# ESP1SH.net
KiCad netlist of a schematic drawn in EAGLE
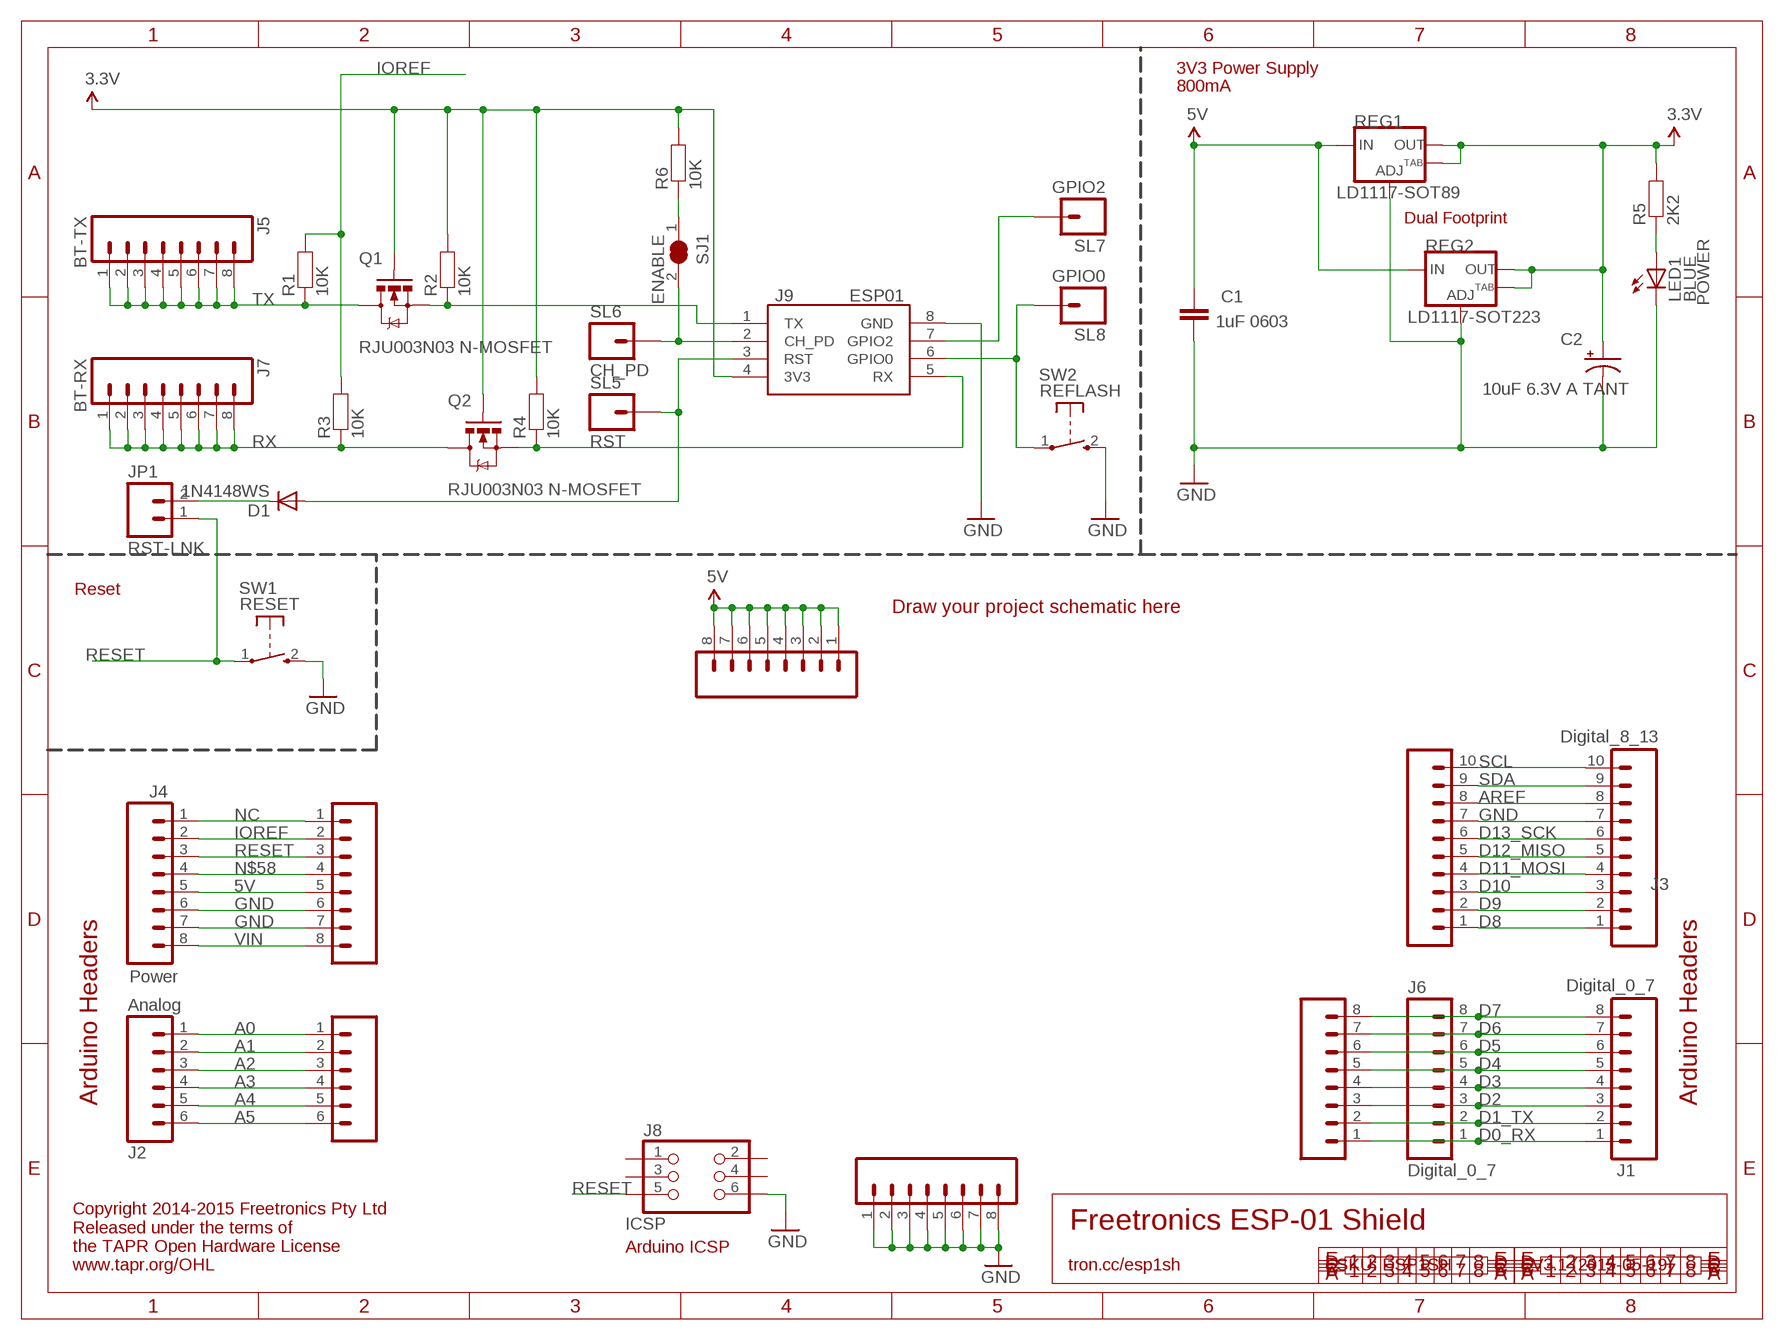
[diagram p0: schematic, sheet 1]

(export (version "E")
  (design (tool "Eeschema 10.0.6"))
  (components
    (comp (ref "C1")
      (value "1uF 0603")
      (footprint "eagle-import:0603")
      (libsource (lib "eagle-import") (part "CAP0603"))
    )
    (comp (ref "C2")
      (value "10uF 6.3V A TANT")
      (footprint "eagle-import:EIA3216")
      (libsource (lib "eagle-import") (part "CAP_POL1206"))
    )
    (comp (ref "D1")
      (value "1N4148WS")
      (footprint "eagle-import:SOD-323")
      (libsource (lib "eagle-import") (part "DIODESOD"))
    )
    (comp (ref "J1")
      (value "Digital_0_7")
      (footprint "eagle-import:1X08")
      (libsource (lib "eagle-import") (part "M08"))
    )
    (comp (ref "J2")
      (value "Analog")
      (footprint "eagle-import:1X06")
      (libsource (lib "eagle-import") (part "M06SIP"))
    )
    (comp (ref "J3")
      (value "Digital_8_13")
      (footprint "eagle-import:1X10")
      (libsource (lib "eagle-import") (part "M100.1"))
    )
    (comp (ref "J4")
      (value "Power")
      (footprint "eagle-import:1X08")
      (libsource (lib "eagle-import") (part "M08"))
    )
    (comp (ref "J5")
      (value "BT-TX")
      (footprint "eagle-import:1X08")
      (libsource (lib "eagle-import") (part "freetronics-original_M08"))
    )
    (comp (ref "J6")
      (value "Digital_0_7")
      (footprint "eagle-import:1X08")
      (libsource (lib "eagle-import") (part "freetronics-original_M08"))
    )
    (comp (ref "J7")
      (value "BT-RX")
      (footprint "eagle-import:1X08")
      (libsource (lib "eagle-import") (part "freetronics-original_M08"))
    )
    (comp (ref "J8")
      (value "ICSP")
      (footprint "eagle-import:2X03PTH")
      (libsource (lib "eagle-import") (part "ICSPPTH"))
    )
    (comp (ref "J9")
      (value "ESP01")
      (footprint "eagle-import:ESP01")
      (libsource (lib "eagle-import") (part "ESP01"))
    )
    (comp (ref "JP1")
      (value "RST-LNK")
      (footprint "eagle-import:1X02")
      (libsource (lib "eagle-import") (part "M02PTH"))
    )
    (comp (ref "LED1")
      (value "BLUE")
      (footprint "eagle-import:LED-0603")
      (libsource (lib "eagle-import") (part "LED0603"))
    )
    (comp (ref "Q1")
      (value "RJU003N03 N-MOSFET")
      (footprint "eagle-import:SOT32-3")
      (libsource (lib "eagle-import") (part "MOSFET-NSOT-323"))
    )
    (comp (ref "Q2")
      (value "RJU003N03 N-MOSFET")
      (footprint "eagle-import:SOT32-3")
      (libsource (lib "eagle-import") (part "MOSFET-NSOT-323"))
    )
    (comp (ref "R1")
      (value "10K")
      (footprint "eagle-import:0603")
      (libsource (lib "eagle-import") (part "RESISTOR0603"))
    )
    (comp (ref "R2")
      (value "10K")
      (footprint "eagle-import:0603")
      (libsource (lib "eagle-import") (part "RESISTOR0603"))
    )
    (comp (ref "R3")
      (value "10K")
      (footprint "eagle-import:0603")
      (libsource (lib "eagle-import") (part "RESISTOR0603"))
    )
    (comp (ref "R4")
      (value "10K")
      (footprint "eagle-import:0603")
      (libsource (lib "eagle-import") (part "RESISTOR0603"))
    )
    (comp (ref "R5")
      (value "2K2")
      (footprint "eagle-import:0603")
      (libsource (lib "eagle-import") (part "RESISTOR0603"))
    )
    (comp (ref "R6")
      (value "10K")
      (footprint "eagle-import:0603")
      (libsource (lib "eagle-import") (part "RESISTOR0603"))
    )
    (comp (ref "REG1")
      (value "LD1117-SOT89")
      (footprint "eagle-import:SOT89")
      (libsource (lib "eagle-import") (part "V_REG_LM1117SOT89"))
    )
    (comp (ref "REG2")
      (value "LD1117-SOT223")
      (footprint "eagle-import:SOT223")
      (libsource (lib "eagle-import") (part "V_REG_LM1117SOT223"))
    )
    (comp (ref "SJ1")
      (value "ENABLE")
      (footprint "eagle-import:SJC")
      (libsource (lib "eagle-import") (part "SJCN"))
    )
    (comp (ref "SL1")
      (value "Digital_0_7")
      (footprint "eagle-import:1X08")
      (libsource (lib "eagle-import") (part "M08"))
    )
    (comp (ref "SL2")
      (value "Analog")
      (footprint "eagle-import:1X06")
      (libsource (lib "eagle-import") (part "M06SIP"))
    )
    (comp (ref "SL3")
      (value "Digital_8_13")
      (footprint "eagle-import:1X10")
      (libsource (lib "eagle-import") (part "M100.1"))
    )
    (comp (ref "SL4")
      (value "Power")
      (footprint "eagle-import:1X08")
      (libsource (lib "eagle-import") (part "M08"))
    )
    (comp (ref "SL5")
      (value "RST")
      (footprint "eagle-import:1X01")
      (libsource (lib "eagle-import") (part "M01PTH"))
    )
    (comp (ref "SL6")
      (value "CH_PD")
      (footprint "eagle-import:1X01")
      (libsource (lib "eagle-import") (part "M01PTH"))
    )
    (comp (ref "SL7")
      (value "GPIO2")
      (footprint "eagle-import:1X01")
      (libsource (lib "eagle-import") (part "M01PTH"))
    )
    (comp (ref "SL8")
      (value "GPIO0")
      (footprint "eagle-import:1X01")
      (libsource (lib "eagle-import") (part "M01PTH"))
    )
    (comp (ref "SL9")
      (value "GND")
      (footprint "eagle-import:1X08")
      (libsource (lib "eagle-import") (part "M08"))
    )
    (comp (ref "SL10")
      (value "5V")
      (footprint "eagle-import:1X08")
      (libsource (lib "eagle-import") (part "M08"))
    )
    (comp (ref "SW1")
      (value "RESET")
      (footprint "eagle-import:TACTILE_SWITCH_SMD_2PIN_TINY")
      (libsource (lib "eagle-import") (part "TAC_SWITCH_2PIN"))
    )
    (comp (ref "SW2")
      (value "REFLASH")
      (footprint "eagle-import:TACTILE_SWITCH_SMD_2PIN_TINY")
      (libsource (lib "eagle-import") (part "TAC_SWITCH_2PIN"))
    )
  )
  (nets
    (net (code "1") (name "/A0") (class "Default")
      (node (ref "J2") (pin "1") (pinfunction "1_1") (pintype "passive"))
      (node (ref "SL2") (pin "1") (pinfunction "1_1") (pintype "passive"))
    )
    (net (code "2") (name "/A1") (class "Default")
      (node (ref "J2") (pin "2") (pinfunction "2_2") (pintype "passive"))
      (node (ref "SL2") (pin "2") (pinfunction "2_2") (pintype "passive"))
    )
    (net (code "3") (name "/A2") (class "Default")
      (node (ref "J2") (pin "3") (pinfunction "3_3") (pintype "passive"))
      (node (ref "SL2") (pin "3") (pinfunction "3_3") (pintype "passive"))
    )
    (net (code "4") (name "/A3") (class "Default")
      (node (ref "J2") (pin "4") (pinfunction "4_4") (pintype "passive"))
      (node (ref "SL2") (pin "4") (pinfunction "4_4") (pintype "passive"))
    )
    (net (code "5") (name "/A4") (class "Default")
      (node (ref "J2") (pin "5") (pinfunction "5_5") (pintype "passive"))
      (node (ref "SL2") (pin "5") (pinfunction "5_5") (pintype "passive"))
    )
    (net (code "6") (name "/A5") (class "Default")
      (node (ref "J2") (pin "6") (pinfunction "6_6") (pintype "passive"))
      (node (ref "SL2") (pin "6") (pinfunction "6_6") (pintype "passive"))
    )
    (net (code "7") (name "/AREF") (class "Default")
      (node (ref "J3") (pin "8") (pinfunction "8_8") (pintype "passive"))
      (node (ref "SL3") (pin "8") (pinfunction "8_8") (pintype "passive"))
    )
    (net (code "8") (name "/D0_RX") (class "Default")
      (node (ref "J1") (pin "1") (pinfunction "1_1") (pintype "passive"))
      (node (ref "J6") (pin "1") (pinfunction "1_1") (pintype "passive"))
      (node (ref "SL1") (pin "1") (pinfunction "1_1") (pintype "passive"))
    )
    (net (code "9") (name "/D1_TX") (class "Default")
      (node (ref "J1") (pin "2") (pinfunction "2_2") (pintype "passive"))
      (node (ref "J6") (pin "2") (pinfunction "2_2") (pintype "passive"))
      (node (ref "SL1") (pin "2") (pinfunction "2_2") (pintype "passive"))
    )
    (net (code "10") (name "/D2") (class "Default")
      (node (ref "J1") (pin "3") (pinfunction "3_3") (pintype "passive"))
      (node (ref "J6") (pin "3") (pinfunction "3_3") (pintype "passive"))
      (node (ref "SL1") (pin "3") (pinfunction "3_3") (pintype "passive"))
    )
    (net (code "11") (name "/D3") (class "Default")
      (node (ref "J1") (pin "4") (pinfunction "4_4") (pintype "passive"))
      (node (ref "J6") (pin "4") (pinfunction "4_4") (pintype "passive"))
      (node (ref "SL1") (pin "4") (pinfunction "4_4") (pintype "passive"))
    )
    (net (code "12") (name "/D4") (class "Default")
      (node (ref "J1") (pin "5") (pinfunction "5_5") (pintype "passive"))
      (node (ref "J6") (pin "5") (pinfunction "5_5") (pintype "passive"))
      (node (ref "SL1") (pin "5") (pinfunction "5_5") (pintype "passive"))
    )
    (net (code "13") (name "/D5") (class "Default")
      (node (ref "J1") (pin "6") (pinfunction "6_6") (pintype "passive"))
      (node (ref "J6") (pin "6") (pinfunction "6_6") (pintype "passive"))
      (node (ref "SL1") (pin "6") (pinfunction "6_6") (pintype "passive"))
    )
    (net (code "14") (name "/D6") (class "Default")
      (node (ref "J1") (pin "7") (pinfunction "7_7") (pintype "passive"))
      (node (ref "J6") (pin "7") (pinfunction "7_7") (pintype "passive"))
      (node (ref "SL1") (pin "7") (pinfunction "7_7") (pintype "passive"))
    )
    (net (code "15") (name "/D7") (class "Default")
      (node (ref "J1") (pin "8") (pinfunction "8_8") (pintype "passive"))
      (node (ref "J6") (pin "8") (pinfunction "8_8") (pintype "passive"))
      (node (ref "SL1") (pin "8") (pinfunction "8_8") (pintype "passive"))
    )
    (net (code "16") (name "/D8") (class "Default")
      (node (ref "J3") (pin "1") (pinfunction "1_1") (pintype "passive"))
      (node (ref "SL3") (pin "1") (pinfunction "1_1") (pintype "passive"))
    )
    (net (code "17") (name "/D9") (class "Default")
      (node (ref "J3") (pin "2") (pinfunction "2_2") (pintype "passive"))
      (node (ref "SL3") (pin "2") (pinfunction "2_2") (pintype "passive"))
    )
    (net (code "18") (name "/D10") (class "Default")
      (node (ref "J3") (pin "3") (pinfunction "3_3") (pintype "passive"))
      (node (ref "SL3") (pin "3") (pinfunction "3_3") (pintype "passive"))
    )
    (net (code "19") (name "/D11_MOSI") (class "Default")
      (node (ref "J3") (pin "4") (pinfunction "4_4") (pintype "passive"))
      (node (ref "SL3") (pin "4") (pinfunction "4_4") (pintype "passive"))
    )
    (net (code "20") (name "/D12_MISO") (class "Default")
      (node (ref "J3") (pin "5") (pinfunction "5_5") (pintype "passive"))
      (node (ref "SL3") (pin "5") (pinfunction "5_5") (pintype "passive"))
    )
    (net (code "21") (name "/D13_SCK") (class "Default")
      (node (ref "J3") (pin "6") (pinfunction "6_6") (pintype "passive"))
      (node (ref "SL3") (pin "6") (pinfunction "6_6") (pintype "passive"))
    )
    (net (code "22") (name "/IOREF") (class "Default")
      (node (ref "J4") (pin "2") (pinfunction "2_2") (pintype "passive"))
      (node (ref "R1") (pin "2") (pinfunction "2_2") (pintype "passive"))
      (node (ref "R3") (pin "2") (pinfunction "2_2") (pintype "passive"))
      (node (ref "SL4") (pin "2") (pinfunction "2_2") (pintype "passive"))
    )
    (net (code "23") (name "/N$58") (class "Default")
      (node (ref "J4") (pin "4") (pinfunction "4_4") (pintype "passive"))
      (node (ref "SL4") (pin "4") (pinfunction "4_4") (pintype "passive"))
    )
    (net (code "24") (name "/NC") (class "Default")
      (node (ref "J4") (pin "1") (pinfunction "1_1") (pintype "passive"))
      (node (ref "SL4") (pin "1") (pinfunction "1_1") (pintype "passive"))
    )
    (net (code "25") (name "/RESET") (class "Default")
      (node (ref "J4") (pin "3") (pinfunction "3_3") (pintype "passive"))
      (node (ref "J8") (pin "5") (pinfunction "5_5") (pintype "passive"))
      (node (ref "JP1") (pin "1") (pinfunction "1_1") (pintype "passive"))
      (node (ref "SL4") (pin "3") (pinfunction "3_3") (pintype "passive"))
      (node (ref "SW1") (pin "1") (pinfunction "P_1") (pintype "passive"))
    )
    (net (code "26") (name "/RX") (class "Default")
      (node (ref "J7") (pin "1") (pinfunction "1_1") (pintype "passive"))
      (node (ref "J7") (pin "2") (pinfunction "2_2") (pintype "passive"))
      (node (ref "J7") (pin "3") (pinfunction "3_3") (pintype "passive"))
      (node (ref "J7") (pin "4") (pinfunction "4_4") (pintype "passive"))
      (node (ref "J7") (pin "5") (pinfunction "5_5") (pintype "passive"))
      (node (ref "J7") (pin "6") (pinfunction "6_6") (pintype "passive"))
      (node (ref "J7") (pin "7") (pinfunction "7_7") (pintype "passive"))
      (node (ref "J7") (pin "8") (pinfunction "8_8") (pintype "passive"))
      (node (ref "Q2") (pin "3") (pinfunction "D_3") (pintype "passive"))
      (node (ref "R3") (pin "1") (pinfunction "1_1") (pintype "passive"))
    )
    (net (code "27") (name "/SCL") (class "Default")
      (node (ref "J3") (pin "10") (pinfunction "10_10") (pintype "passive"))
      (node (ref "SL3") (pin "10") (pinfunction "10_10") (pintype "passive"))
    )
    (net (code "28") (name "/SDA") (class "Default")
      (node (ref "J3") (pin "9") (pinfunction "9_9") (pintype "passive"))
      (node (ref "SL3") (pin "9") (pinfunction "9_9") (pintype "passive"))
    )
    (net (code "29") (name "/TX") (class "Default")
      (node (ref "J5") (pin "1") (pinfunction "1_1") (pintype "passive"))
      (node (ref "J5") (pin "2") (pinfunction "2_2") (pintype "passive"))
      (node (ref "J5") (pin "3") (pinfunction "3_3") (pintype "passive"))
      (node (ref "J5") (pin "4") (pinfunction "4_4") (pintype "passive"))
      (node (ref "J5") (pin "5") (pinfunction "5_5") (pintype "passive"))
      (node (ref "J5") (pin "6") (pinfunction "6_6") (pintype "passive"))
      (node (ref "J5") (pin "7") (pinfunction "7_7") (pintype "passive"))
      (node (ref "J5") (pin "8") (pinfunction "8_8") (pintype "passive"))
      (node (ref "Q1") (pin "3") (pinfunction "D_3") (pintype "passive"))
      (node (ref "R1") (pin "1") (pinfunction "1_1") (pintype "passive"))
    )
    (net (code "30") (name "/VIN") (class "Default")
      (node (ref "J4") (pin "8") (pinfunction "8_8") (pintype "passive"))
      (node (ref "SL4") (pin "8") (pinfunction "8_8") (pintype "passive"))
    )
    (net (code "31") (name "3.3V") (class "Default")
      (node (ref "C2") (pin "A") (pinfunction "+_A") (pintype "passive"))
      (node (ref "J9") (pin "4") (pinfunction "3V3_4") (pintype "bidirectional"))
      (node (ref "Q1") (pin "1") (pinfunction "G_1") (pintype "passive"))
      (node (ref "Q2") (pin "1") (pinfunction "G_1") (pintype "passive"))
      (node (ref "R2") (pin "2") (pinfunction "2_2") (pintype "passive"))
      (node (ref "R4") (pin "2") (pinfunction "2_2") (pintype "passive"))
      (node (ref "R5") (pin "2") (pinfunction "2_2") (pintype "passive"))
      (node (ref "R6") (pin "2") (pinfunction "2_2") (pintype "passive"))
      (node (ref "REG1") (pin "2") (pinfunction "OUT_2") (pintype "output"))
      (node (ref "REG1") (pin "4") (pinfunction "OUT_4") (pintype "output"))
      (node (ref "REG2") (pin "2") (pinfunction "OUT_2") (pintype "output"))
      (node (ref "REG2") (pin "4") (pinfunction "OUT_4") (pintype "output"))
    )
    (net (code "32") (name "5V") (class "Default")
      (node (ref "C1") (pin "1") (pinfunction "1_1") (pintype "passive"))
      (node (ref "J4") (pin "5") (pinfunction "5_5") (pintype "passive"))
      (node (ref "REG1") (pin "3") (pinfunction "IN_3") (pintype "input"))
      (node (ref "REG2") (pin "3") (pinfunction "IN_3") (pintype "input"))
      (node (ref "SL10") (pin "1") (pinfunction "1_1") (pintype "passive"))
      (node (ref "SL10") (pin "2") (pinfunction "2_2") (pintype "passive"))
      (node (ref "SL10") (pin "3") (pinfunction "3_3") (pintype "passive"))
      (node (ref "SL10") (pin "4") (pinfunction "4_4") (pintype "passive"))
      (node (ref "SL10") (pin "5") (pinfunction "5_5") (pintype "passive"))
      (node (ref "SL10") (pin "6") (pinfunction "6_6") (pintype "passive"))
      (node (ref "SL10") (pin "7") (pinfunction "7_7") (pintype "passive"))
      (node (ref "SL10") (pin "8") (pinfunction "8_8") (pintype "passive"))
      (node (ref "SL4") (pin "5") (pinfunction "5_5") (pintype "passive"))
    )
    (net (code "33") (name "GND") (class "Default")
      (node (ref "C1") (pin "2") (pinfunction "2_2") (pintype "passive"))
      (node (ref "C2") (pin "C") (pinfunction "-_C") (pintype "passive"))
      (node (ref "J3") (pin "7") (pinfunction "7_7") (pintype "passive"))
      (node (ref "J4") (pin "6") (pinfunction "6_6") (pintype "passive"))
      (node (ref "J4") (pin "7") (pinfunction "7_7") (pintype "passive"))
      (node (ref "J8") (pin "6") (pinfunction "6_6") (pintype "passive"))
      (node (ref "J9") (pin "8") (pinfunction "GND_8") (pintype "bidirectional"))
      (node (ref "LED1") (pin "C") (pinfunction "C_C") (pintype "passive"))
      (node (ref "REG1") (pin "1") (pinfunction "ADJ_1") (pintype "input"))
      (node (ref "REG2") (pin "1") (pinfunction "ADJ_1") (pintype "input"))
      (node (ref "SL3") (pin "7") (pinfunction "7_7") (pintype "passive"))
      (node (ref "SL4") (pin "6") (pinfunction "6_6") (pintype "passive"))
      (node (ref "SL4") (pin "7") (pinfunction "7_7") (pintype "passive"))
      (node (ref "SL9") (pin "1") (pinfunction "1_1") (pintype "passive"))
      (node (ref "SL9") (pin "2") (pinfunction "2_2") (pintype "passive"))
      (node (ref "SL9") (pin "3") (pinfunction "3_3") (pintype "passive"))
      (node (ref "SL9") (pin "4") (pinfunction "4_4") (pintype "passive"))
      (node (ref "SL9") (pin "5") (pinfunction "5_5") (pintype "passive"))
      (node (ref "SL9") (pin "6") (pinfunction "6_6") (pintype "passive"))
      (node (ref "SL9") (pin "7") (pinfunction "7_7") (pintype "passive"))
      (node (ref "SL9") (pin "8") (pinfunction "8_8") (pintype "passive"))
      (node (ref "SW1") (pin "2") (pinfunction "S_2") (pintype "passive"))
      (node (ref "SW2") (pin "2") (pinfunction "S_2") (pintype "passive"))
    )
    (net (code "34") (name "Net-(D1-A)") (class "Default")
      (node (ref "D1") (pin "2") (pinfunction "A_2") (pintype "passive"))
      (node (ref "J9") (pin "3") (pinfunction "RST_3") (pintype "bidirectional"))
      (node (ref "SL5") (pin "1") (pinfunction "1_1") (pintype "passive"))
    )
    (net (code "35") (name "Net-(D1-C)") (class "Default")
      (node (ref "D1") (pin "1") (pinfunction "C_1") (pintype "passive"))
      (node (ref "JP1") (pin "2") (pinfunction "2_2") (pintype "passive"))
    )
    (net (code "36") (name "Net-(J9-CH_PD)") (class "Default")
      (node (ref "J9") (pin "2") (pinfunction "CH_PD_2") (pintype "bidirectional"))
      (node (ref "SJ1") (pin "2") (pinfunction "2_2") (pintype "passive"))
      (node (ref "SL6") (pin "1") (pinfunction "1_1") (pintype "passive"))
    )
    (net (code "37") (name "Net-(J9-GPIO0)") (class "Default")
      (node (ref "J9") (pin "6") (pinfunction "GPIO0_6") (pintype "bidirectional"))
      (node (ref "SL8") (pin "1") (pinfunction "1_1") (pintype "passive"))
      (node (ref "SW2") (pin "1") (pinfunction "P_1") (pintype "passive"))
    )
    (net (code "38") (name "Net-(J9-GPIO2)") (class "Default")
      (node (ref "J9") (pin "7") (pinfunction "GPIO2_7") (pintype "bidirectional"))
      (node (ref "SL7") (pin "1") (pinfunction "1_1") (pintype "passive"))
    )
    (net (code "39") (name "Net-(J9-RX)") (class "Default")
      (node (ref "J9") (pin "5") (pinfunction "RX_5") (pintype "bidirectional"))
      (node (ref "Q2") (pin "2") (pinfunction "S_2") (pintype "passive"))
      (node (ref "R4") (pin "1") (pinfunction "1_1") (pintype "passive"))
    )
    (net (code "40") (name "Net-(J9-TX)") (class "Default")
      (node (ref "J9") (pin "1") (pinfunction "TX_1") (pintype "bidirectional"))
      (node (ref "Q1") (pin "2") (pinfunction "S_2") (pintype "passive"))
      (node (ref "R2") (pin "1") (pinfunction "1_1") (pintype "passive"))
    )
    (net (code "41") (name "Net-(LED1-PadA)") (class "Default")
      (node (ref "LED1") (pin "A") (pinfunction "A_A") (pintype "passive"))
      (node (ref "R5") (pin "1") (pinfunction "1_1") (pintype "passive"))
    )
    (net (code "42") (name "Net-(R6-Pad1)") (class "Default")
      (node (ref "R6") (pin "1") (pinfunction "1_1") (pintype "passive"))
      (node (ref "SJ1") (pin "1") (pinfunction "1_1") (pintype "passive"))
    )
    (net (code "43") (name "unconnected-(J8-Pad1)") (class "Default")
      (node (ref "J8") (pin "1") (pinfunction "1_1") (pintype "passive"))
    )
    (net (code "44") (name "unconnected-(J8-Pad2)") (class "Default")
      (node (ref "J8") (pin "2") (pinfunction "2_2") (pintype "passive"))
    )
    (net (code "45") (name "unconnected-(J8-Pad3)") (class "Default")
      (node (ref "J8") (pin "3") (pinfunction "3_3") (pintype "passive"))
    )
    (net (code "46") (name "unconnected-(J8-Pad4)") (class "Default")
      (node (ref "J8") (pin "4") (pinfunction "4_4") (pintype "passive"))
    )
  )
)
